# generator.net
KiCad netlist of a schematic drawn in EAGLE
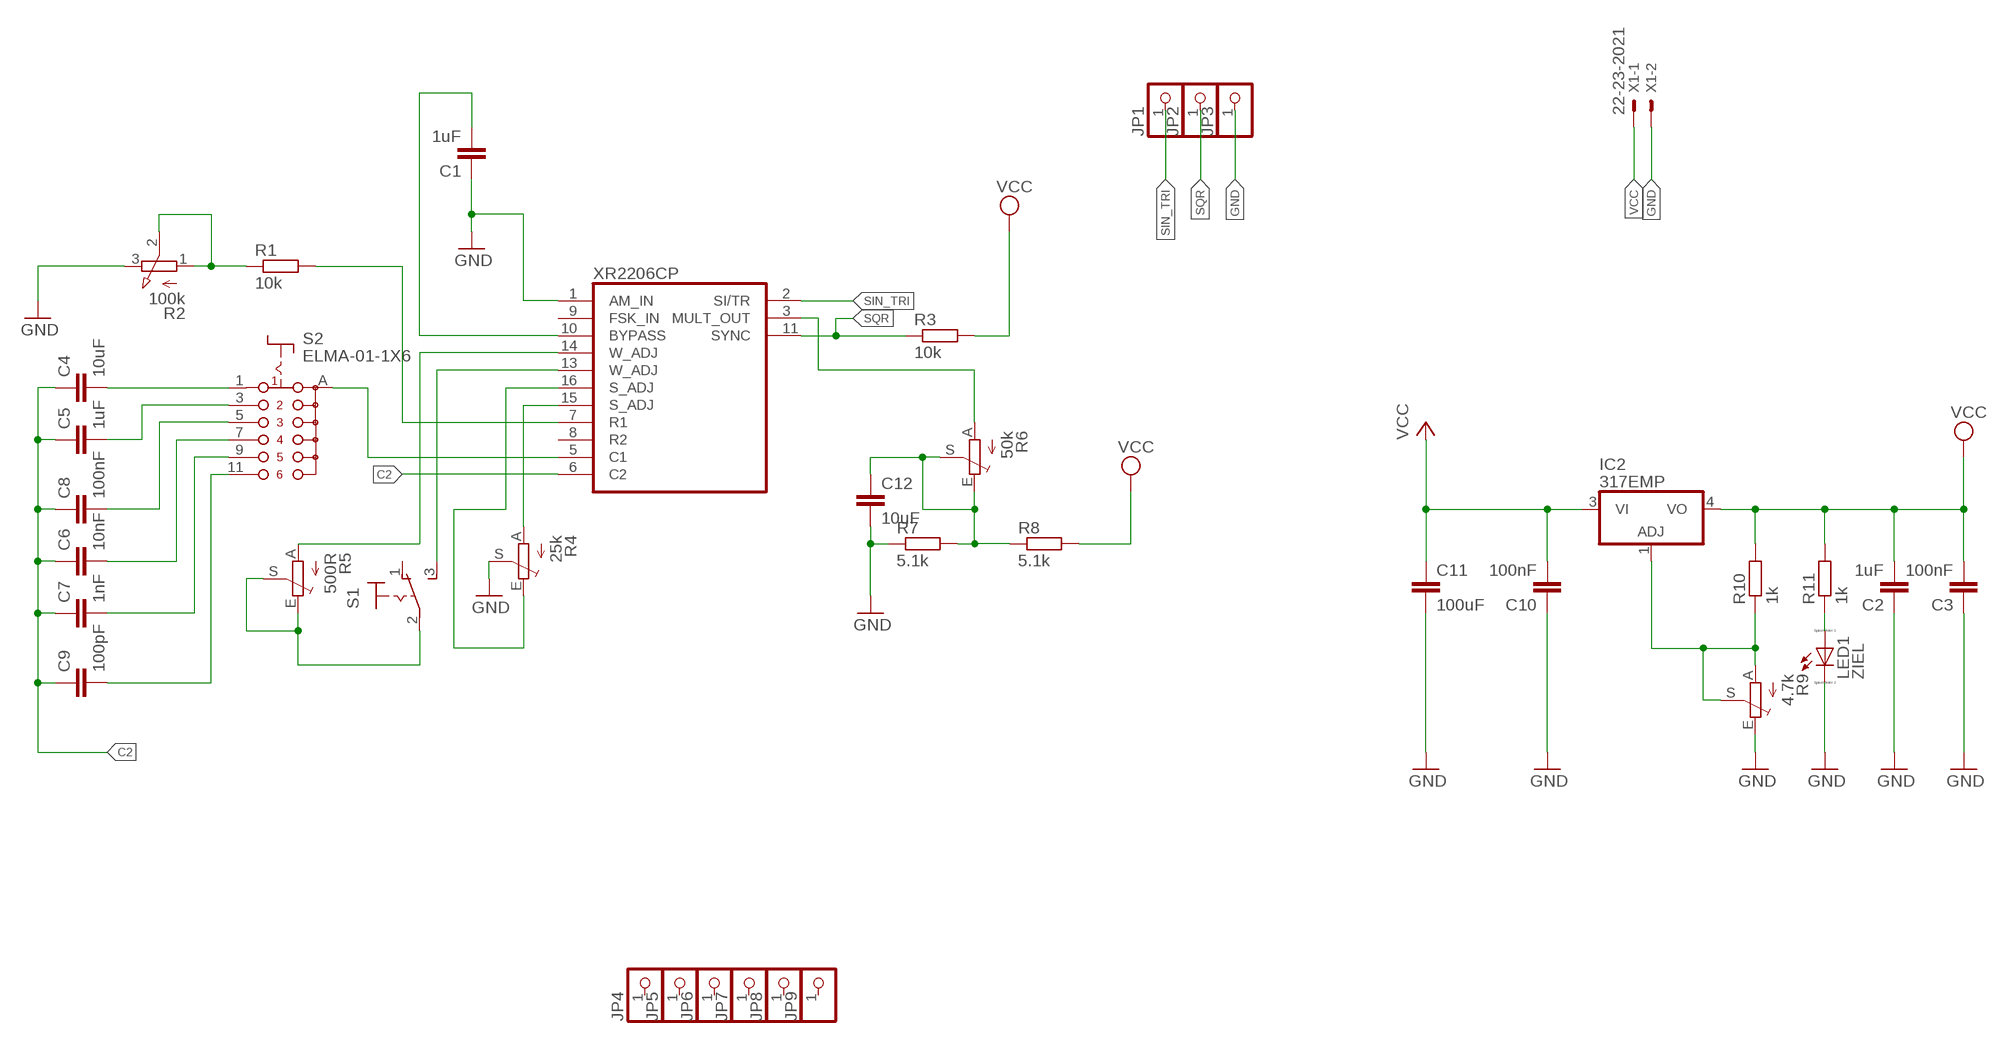
[diagram p0: schematic, sheet 1]

(export (version "E")
  (design (tool "Eeschema 10.0.6"))
  (components
    (comp (ref "C1")
      (value "1uF")
      (footprint "eagle-import:C0805")
      (libsource (lib "eagle-import") (part "C-EUC0805"))
    )
    (comp (ref "C2")
      (value "1uF")
      (footprint "eagle-import:C0805")
      (libsource (lib "eagle-import") (part "C-EUC0805"))
    )
    (comp (ref "C3")
      (value "100nF")
      (footprint "eagle-import:C0805")
      (libsource (lib "eagle-import") (part "C-EUC0805"))
    )
    (comp (ref "C4")
      (value "10uF")
      (footprint "eagle-import:C0805")
      (libsource (lib "eagle-import") (part "C-EUC0805"))
    )
    (comp (ref "C5")
      (value "1uF")
      (footprint "eagle-import:C0805")
      (libsource (lib "eagle-import") (part "C-EUC0805"))
    )
    (comp (ref "C6")
      (value "10nF")
      (footprint "eagle-import:C0805")
      (libsource (lib "eagle-import") (part "C-EUC0805"))
    )
    (comp (ref "C7")
      (value "1nF")
      (footprint "eagle-import:C0805")
      (libsource (lib "eagle-import") (part "C-EUC0805"))
    )
    (comp (ref "C8")
      (value "100nF")
      (footprint "eagle-import:C0805")
      (libsource (lib "eagle-import") (part "C-EUC0805"))
    )
    (comp (ref "C9")
      (value "100pF")
      (footprint "eagle-import:C0805")
      (libsource (lib "eagle-import") (part "C-EUC0805"))
    )
    (comp (ref "C10")
      (value "100nF")
      (footprint "eagle-import:C0805")
      (libsource (lib "eagle-import") (part "C-EUC0805"))
    )
    (comp (ref "C11")
      (value "100uF")
      (footprint "eagle-import:C0805")
      (libsource (lib "eagle-import") (part "C-EUC0805"))
    )
    (comp (ref "C12")
      (value "10uF")
      (footprint "eagle-import:C0805")
      (libsource (lib "eagle-import") (part "C-EUC0805"))
    )
    (comp (ref "IC2")
      (value "317EMP")
      (footprint "eagle-import:SOT223")
      (libsource (lib "eagle-import") (part "317EMP"))
    )
    (comp (ref "JP1")
      (value "PINHD-1X1")
      (footprint "eagle-import:1X01")
      (libsource (lib "eagle-import") (part "PINHD-1X1"))
    )
    (comp (ref "JP2")
      (value "PINHD-1X1")
      (footprint "eagle-import:1X01")
      (libsource (lib "eagle-import") (part "PINHD-1X1"))
    )
    (comp (ref "JP3")
      (value "PINHD-1X1")
      (footprint "eagle-import:1X01")
      (libsource (lib "eagle-import") (part "PINHD-1X1"))
    )
    (comp (ref "JP4")
      (value "PINHD-1X1")
      (footprint "eagle-import:1X01")
      (libsource (lib "eagle-import") (part "PINHD-1X1"))
    )
    (comp (ref "JP5")
      (value "PINHD-1X1")
      (footprint "eagle-import:1X01")
      (libsource (lib "eagle-import") (part "PINHD-1X1"))
    )
    (comp (ref "JP6")
      (value "PINHD-1X1")
      (footprint "eagle-import:1X01")
      (libsource (lib "eagle-import") (part "PINHD-1X1"))
    )
    (comp (ref "JP7")
      (value "PINHD-1X1")
      (footprint "eagle-import:1X01")
      (libsource (lib "eagle-import") (part "PINHD-1X1"))
    )
    (comp (ref "JP8")
      (value "PINHD-1X1")
      (footprint "eagle-import:1X01")
      (libsource (lib "eagle-import") (part "PINHD-1X1"))
    )
    (comp (ref "JP9")
      (value "PINHD-1X1")
      (footprint "eagle-import:1X01")
      (libsource (lib "eagle-import") (part "PINHD-1X1"))
    )
    (comp (ref "LED1")
      (value "ZIEL")
      (footprint "eagle-import:LED_1206")
      (libsource (lib "eagle-import") (part "LED_E"))
    )
    (comp (ref "R1")
      (value "10k")
      (footprint "eagle-import:R0805")
      (libsource (lib "eagle-import") (part "R-EU_R0805"))
    )
    (comp (ref "R2")
      (value "100k")
      (footprint "eagle-import:3RP_1610N")
      (libsource (lib "eagle-import") (part "3RP/1610N"))
    )
    (comp (ref "R3")
      (value "10k")
      (footprint "eagle-import:R0805")
      (libsource (lib "eagle-import") (part "R-EU_R0805"))
    )
    (comp (ref "R4")
      (value "25k")
      (footprint "eagle-import:PT-SPIN")
      (libsource (lib "eagle-import") (part "TRIM_EU-PTSPIN"))
    )
    (comp (ref "R5")
      (value "500R")
      (footprint "eagle-import:PT-SPIN")
      (libsource (lib "eagle-import") (part "TRIM_EU-PTSPIN"))
    )
    (comp (ref "R6")
      (value "50k")
      (footprint "eagle-import:PT-SPIN")
      (libsource (lib "eagle-import") (part "TRIM_EU-PTSPIN"))
    )
    (comp (ref "R7")
      (value "5.1k")
      (footprint "eagle-import:R0805")
      (libsource (lib "eagle-import") (part "R-EU_R0805"))
    )
    (comp (ref "R8")
      (value "5.1k")
      (footprint "eagle-import:R0805")
      (libsource (lib "eagle-import") (part "R-EU_R0805"))
    )
    (comp (ref "R9")
      (value "4.7k")
      (footprint "eagle-import:PT-SPIN")
      (libsource (lib "eagle-import") (part "TRIM_EU-PTSPIN"))
    )
    (comp (ref "R10")
      (value "1k")
      (footprint "eagle-import:R0805")
      (libsource (lib "eagle-import") (part "R-EU_R0805"))
    )
    (comp (ref "R11")
      (value "1k")
      (footprint "eagle-import:R0805")
      (libsource (lib "eagle-import") (part "R-EU_R0805"))
    )
    (comp (ref "S1")
      (value "320-916")
      (footprint "eagle-import:320-916")
      (libsource (lib "eagle-import") (part "320-916"))
    )
    (comp (ref "S2")
      (value "ELMA-01-1X6")
      (footprint "eagle-import:ELMA-01-1X6")
      (libsource (lib "eagle-import") (part "ELMA-01-1X6"))
    )
    (comp (ref "X1")
      (value "22-23-2021")
      (footprint "eagle-import:22-23-2021")
      (fields (field (name "MF") "MOLEX"))
      (libsource (lib "eagle-import") (part "22-23-2021"))
    )
    (comp (ref "XR2206CP")
      (value "XR-2206")
      (footprint "eagle-import:DIL16")
      (libsource (lib "eagle-import") (part "XR-2206"))
    )
  )
  (nets
    (net (code "1") (name "C2") (class "Default")
      (node (ref "C4") (pin "1") (pinfunction "1_1") (pintype "passive"))
      (node (ref "C5") (pin "1") (pinfunction "1_1") (pintype "passive"))
      (node (ref "C6") (pin "1") (pinfunction "1_1") (pintype "passive"))
      (node (ref "C7") (pin "1") (pinfunction "1_1") (pintype "passive"))
      (node (ref "C8") (pin "1") (pinfunction "1_1") (pintype "passive"))
      (node (ref "C9") (pin "1") (pinfunction "1_1") (pintype "passive"))
      (node (ref "XR2206CP") (pin "6") (pinfunction "C2_6") (pintype "input"))
    )
    (net (code "2") (name "GND") (class "Default")
      (node (ref "C1") (pin "1") (pinfunction "1_1") (pintype "passive"))
      (node (ref "C10") (pin "1") (pinfunction "1_1") (pintype "passive"))
      (node (ref "C11") (pin "2") (pinfunction "2_2") (pintype "passive"))
      (node (ref "C12") (pin "2") (pinfunction "2_2") (pintype "passive"))
      (node (ref "C2") (pin "1") (pinfunction "1_1") (pintype "passive"))
      (node (ref "C3") (pin "1") (pinfunction "1_1") (pintype "passive"))
      (node (ref "JP3") (pin "1") (pinfunction "1_1") (pintype "passive"))
      (node (ref "LED1") (pin "C") (pinfunction "C_C") (pintype "passive"))
      (node (ref "R2") (pin "3") (pinfunction "E_3") (pintype "passive"))
      (node (ref "R4") (pin "S") (pinfunction "S_S") (pintype "passive"))
      (node (ref "R7") (pin "1") (pinfunction "1_1") (pintype "passive"))
      (node (ref "R9") (pin "E") (pinfunction "E_E") (pintype "passive"))
      (node (ref "X1") (pin "2") (pinfunction "S_2") (pintype "passive"))
      (node (ref "XR2206CP") (pin "1") (pinfunction "AM_IN_1") (pintype "input"))
    )
    (net (code "3") (name "Net-(C4-Pad2)") (class "Default")
      (node (ref "C4") (pin "2") (pinfunction "2_2") (pintype "passive"))
      (node (ref "S2") (pin "1") (pinfunction "1_1") (pintype "passive"))
    )
    (net (code "4") (name "Net-(C12-Pad1)") (class "Default")
      (node (ref "C12") (pin "1") (pinfunction "1_1") (pintype "passive"))
      (node (ref "R6") (pin "E") (pinfunction "E_E") (pintype "passive"))
      (node (ref "R6") (pin "S") (pinfunction "S_S") (pintype "passive"))
      (node (ref "R7") (pin "2") (pinfunction "2_2") (pintype "passive"))
      (node (ref "R8") (pin "1") (pinfunction "1_1") (pintype "passive"))
    )
    (net (code "5") (name "Net-(IC2-ADJ)") (class "Default")
      (node (ref "IC2") (pin "1") (pinfunction "ADJ_1") (pintype "input"))
      (node (ref "R10") (pin "1") (pinfunction "1_1") (pintype "passive"))
      (node (ref "R9") (pin "A") (pinfunction "A_A") (pintype "passive"))
      (node (ref "R9") (pin "S") (pinfunction "S_S") (pintype "passive"))
    )
    (net (code "6") (name "Net-(LED1-PadA)") (class "Default")
      (node (ref "LED1") (pin "A") (pinfunction "A_A") (pintype "passive"))
      (node (ref "R11") (pin "1") (pinfunction "1_1") (pintype "passive"))
    )
    (net (code "7") (name "Net-(R2-A)") (class "Default")
      (node (ref "R1") (pin "1") (pinfunction "1_1") (pintype "passive"))
      (node (ref "R2") (pin "1") (pinfunction "A_1") (pintype "passive"))
      (node (ref "R2") (pin "2") (pinfunction "S_2") (pintype "passive"))
    )
    (net (code "8") (name "Net-(R4-PadA)") (class "Default")
      (node (ref "R4") (pin "A") (pinfunction "A_A") (pintype "passive"))
      (node (ref "XR2206CP") (pin "15") (pinfunction "S_ADJ_15") (pintype "input"))
    )
    (net (code "9") (name "Net-(R4-PadE)") (class "Default")
      (node (ref "R4") (pin "E") (pinfunction "E_E") (pintype "passive"))
      (node (ref "XR2206CP") (pin "16") (pinfunction "S_ADJ_16") (pintype "input"))
    )
    (net (code "10") (name "Net-(R5-PadA)") (class "Default")
      (node (ref "R5") (pin "A") (pinfunction "A_A") (pintype "passive"))
      (node (ref "XR2206CP") (pin "14") (pinfunction "W_ADJ_14") (pintype "input"))
    )
    (net (code "11") (name "Net-(S1-P)") (class "Default")
      (node (ref "R5") (pin "E") (pinfunction "E_E") (pintype "passive"))
      (node (ref "R5") (pin "S") (pinfunction "S_S") (pintype "passive"))
      (node (ref "S1") (pin "2") (pinfunction "P_2") (pintype "passive"))
    )
    (net (code "12") (name "Net-(S1-S)") (class "Default")
      (node (ref "S1") (pin "3") (pinfunction "S_3") (pintype "passive"))
      (node (ref "XR2206CP") (pin "13") (pinfunction "W_ADJ_13") (pintype "input"))
    )
    (net (code "13") (name "Net-(S2-2)") (class "Default")
      (node (ref "C5") (pin "2") (pinfunction "2_2") (pintype "passive"))
      (node (ref "S2") (pin "3") (pinfunction "2_3") (pintype "passive"))
    )
    (net (code "14") (name "Net-(S2-3)") (class "Default")
      (node (ref "C8") (pin "2") (pinfunction "2_2") (pintype "passive"))
      (node (ref "S2") (pin "5") (pinfunction "3_5") (pintype "passive"))
    )
    (net (code "15") (name "Net-(S2-4)") (class "Default")
      (node (ref "C6") (pin "2") (pinfunction "2_2") (pintype "passive"))
      (node (ref "S2") (pin "7") (pinfunction "4_7") (pintype "passive"))
    )
    (net (code "16") (name "Net-(S2-5)") (class "Default")
      (node (ref "C7") (pin "2") (pinfunction "2_2") (pintype "passive"))
      (node (ref "S2") (pin "9") (pinfunction "5_9") (pintype "passive"))
    )
    (net (code "17") (name "Net-(S2-6)") (class "Default")
      (node (ref "C9") (pin "2") (pinfunction "2_2") (pintype "passive"))
      (node (ref "S2") (pin "11") (pinfunction "6_11") (pintype "passive"))
    )
    (net (code "18") (name "Net-(S2-S)") (class "Default")
      (node (ref "S2") (pin "A") (pinfunction "S_A") (pintype "passive"))
      (node (ref "XR2206CP") (pin "5") (pinfunction "C1_5") (pintype "input"))
    )
    (net (code "19") (name "Net-(XR2206CPA-BYPASS)") (class "Default")
      (node (ref "C1") (pin "2") (pinfunction "2_2") (pintype "passive"))
      (node (ref "XR2206CP") (pin "10") (pinfunction "BYPASS_10") (pintype "input"))
    )
    (net (code "20") (name "Net-(XR2206CPA-MULT_OUT)") (class "Default")
      (node (ref "R6") (pin "A") (pinfunction "A_A") (pintype "passive"))
      (node (ref "XR2206CP") (pin "3") (pinfunction "MULT_OUT_3") (pintype "output"))
    )
    (net (code "21") (name "Net-(XR2206CPA-R1)") (class "Default")
      (node (ref "R1") (pin "2") (pinfunction "2_2") (pintype "passive"))
      (node (ref "XR2206CP") (pin "7") (pinfunction "R1_7") (pintype "input"))
    )
    (net (code "22") (name "SIN_TRI") (class "Default")
      (node (ref "JP1") (pin "1") (pinfunction "1_1") (pintype "passive"))
      (node (ref "XR2206CP") (pin "2") (pinfunction "SI/TR_2") (pintype "output"))
    )
    (net (code "23") (name "SQR") (class "Default")
      (node (ref "JP2") (pin "1") (pinfunction "1_1") (pintype "passive"))
      (node (ref "R3") (pin "1") (pinfunction "1_1") (pintype "passive"))
      (node (ref "XR2206CP") (pin "11") (pinfunction "SYNC_11") (pintype "output"))
    )
    (net (code "24") (name "VCC") (class "Default")
      (node (ref "C10") (pin "2") (pinfunction "2_2") (pintype "passive"))
      (node (ref "C11") (pin "1") (pinfunction "1_1") (pintype "passive"))
      (node (ref "C2") (pin "2") (pinfunction "2_2") (pintype "passive"))
      (node (ref "C3") (pin "2") (pinfunction "2_2") (pintype "passive"))
      (node (ref "IC2") (pin "3") (pinfunction "VI_3") (pintype "input"))
      (node (ref "IC2") (pin "4") (pinfunction "VO_4") (pintype "passive"))
      (node (ref "R10") (pin "2") (pinfunction "2_2") (pintype "passive"))
      (node (ref "R11") (pin "2") (pinfunction "2_2") (pintype "passive"))
      (node (ref "R3") (pin "2") (pinfunction "2_2") (pintype "passive"))
      (node (ref "R8") (pin "2") (pinfunction "2_2") (pintype "passive"))
      (node (ref "X1") (pin "1") (pinfunction "S_1") (pintype "passive"))
    )
    (net (code "25") (name "unconnected-(JP4-Pad1)") (class "Default")
      (node (ref "JP4") (pin "1") (pinfunction "1_1") (pintype "passive"))
    )
    (net (code "26") (name "unconnected-(JP5-Pad1)") (class "Default")
      (node (ref "JP5") (pin "1") (pinfunction "1_1") (pintype "passive"))
    )
    (net (code "27") (name "unconnected-(JP6-Pad1)") (class "Default")
      (node (ref "JP6") (pin "1") (pinfunction "1_1") (pintype "passive"))
    )
    (net (code "28") (name "unconnected-(JP7-Pad1)") (class "Default")
      (node (ref "JP7") (pin "1") (pinfunction "1_1") (pintype "passive"))
    )
    (net (code "29") (name "unconnected-(JP8-Pad1)") (class "Default")
      (node (ref "JP8") (pin "1") (pinfunction "1_1") (pintype "passive"))
    )
    (net (code "30") (name "unconnected-(JP9-Pad1)") (class "Default")
      (node (ref "JP9") (pin "1") (pinfunction "1_1") (pintype "passive"))
    )
    (net (code "31") (name "unconnected-(S1-O-Pad1)") (class "Default")
      (node (ref "S1") (pin "1") (pinfunction "O_1") (pintype "passive"))
    )
    (net (code "32") (name "unconnected-(XR2206CPA-FSK_IN-Pad9)") (class "Default")
      (node (ref "XR2206CP") (pin "9") (pinfunction "FSK_IN_9") (pintype "input"))
    )
    (net (code "33") (name "unconnected-(XR2206CPA-R2-Pad8)") (class "Default")
      (node (ref "XR2206CP") (pin "8") (pinfunction "R2_8") (pintype "input"))
    )
  )
)
